# DSO_RAM.net
KiCad netlist of a schematic drawn in Altium Designer
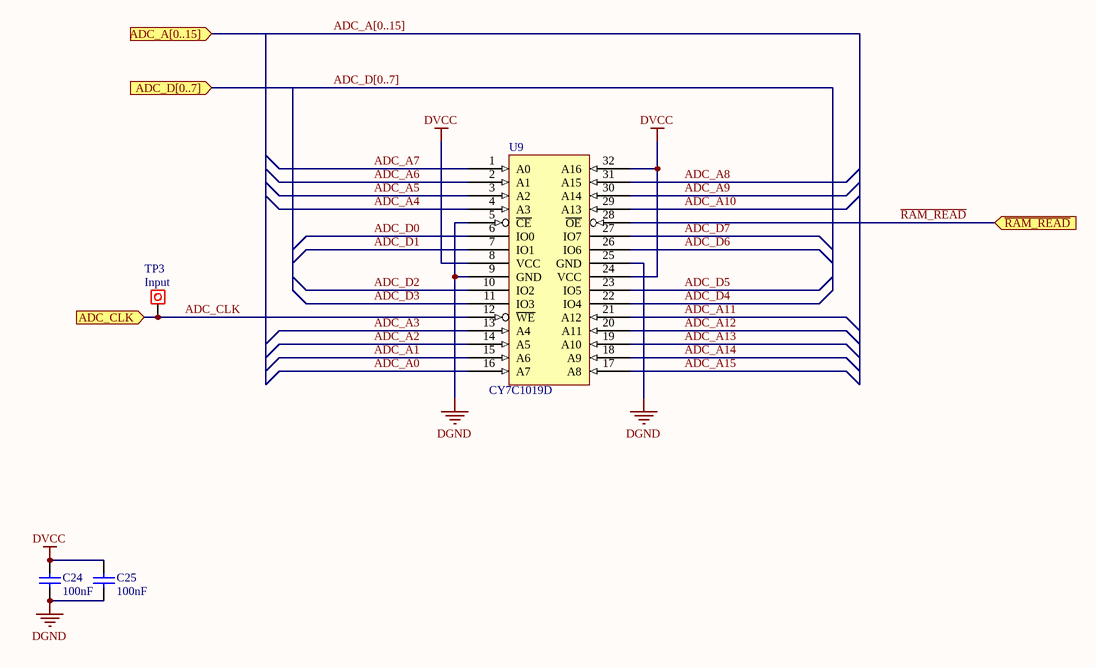
[diagram p0: DSO_RAM.SchDoc]

(export (version "E")
  (design (tool "Eeschema 10.0.6"))
  (components
    (comp (ref "C24")
      (value "100nF")
      (footprint "0805C")
      (description "Capacitor")
      (fields (field (name "REVIEWED BY") "RM - 2018/08/05"))
      (libsource (lib "DSO") (part "C"))
    )
    (comp (ref "C25")
      (value "100nF")
      (footprint "0805C")
      (description "Capacitor")
      (fields (field (name "REVIEWED BY") "RM - 2018/08/05"))
      (libsource (lib "DSO") (part "C"))
    )
    (comp (ref "TP3")
      (value "Input")
      (footprint "Testpoin")
      (description "Pad")
      (fields (field (name "Comment") "INPUT"))
      (libsource (lib "DSO") (part "Test Point"))
    )
    (comp (ref "U9")
      (value "CY7C1019D")
      (footprint "TSOP-32")
      (description "SRAM 128k x 8")
      (fields (field (name "REVIEWED BY") "RM - 2018/08/05"))
      (libsource (lib "DSO") (part "CY7C1019D"))
    )
  )
  (nets
    (net (code "1") (name "/ADC_A0") (class "Default")
      (node (ref "U9") (pin "16") (pinfunction "A7_16") (pintype "input"))
    )
    (net (code "2") (name "/ADC_A1") (class "Default")
      (node (ref "U9") (pin "15") (pinfunction "A6_15") (pintype "input"))
    )
    (net (code "3") (name "/ADC_A2") (class "Default")
      (node (ref "U9") (pin "14") (pinfunction "A5_14") (pintype "input"))
    )
    (net (code "4") (name "/ADC_A3") (class "Default")
      (node (ref "U9") (pin "13") (pinfunction "A4_13") (pintype "input"))
    )
    (net (code "5") (name "/ADC_A4") (class "Default")
      (node (ref "U9") (pin "4") (pinfunction "A3_4") (pintype "input"))
    )
    (net (code "6") (name "/ADC_A5") (class "Default")
      (node (ref "U9") (pin "3") (pinfunction "A2_3") (pintype "input"))
    )
    (net (code "7") (name "/ADC_A6") (class "Default")
      (node (ref "U9") (pin "2") (pinfunction "A1_2") (pintype "input"))
    )
    (net (code "8") (name "/ADC_A7") (class "Default")
      (node (ref "U9") (pin "1") (pinfunction "A0_1") (pintype "input"))
    )
    (net (code "9") (name "/ADC_A8") (class "Default")
      (node (ref "U9") (pin "31") (pinfunction "A15_31") (pintype "input"))
    )
    (net (code "10") (name "/ADC_A9") (class "Default")
      (node (ref "U9") (pin "30") (pinfunction "A14_30") (pintype "input"))
    )
    (net (code "11") (name "/ADC_A10") (class "Default")
      (node (ref "U9") (pin "29") (pinfunction "A13_29") (pintype "input"))
    )
    (net (code "12") (name "/ADC_A11") (class "Default")
      (node (ref "U9") (pin "21") (pinfunction "A12_21") (pintype "input"))
    )
    (net (code "13") (name "/ADC_A12") (class "Default")
      (node (ref "U9") (pin "20") (pinfunction "A11_20") (pintype "input"))
    )
    (net (code "14") (name "/ADC_A13") (class "Default")
      (node (ref "U9") (pin "19") (pinfunction "A10_19") (pintype "input"))
    )
    (net (code "15") (name "/ADC_A14") (class "Default")
      (node (ref "U9") (pin "18") (pinfunction "A9_18") (pintype "input"))
    )
    (net (code "16") (name "/ADC_A15") (class "Default")
      (node (ref "U9") (pin "17") (pinfunction "A8_17") (pintype "input"))
    )
    (net (code "18") (name "/ADC_CLK") (class "Default")
      (node (ref "TP3") (pin "1") (pintype "passive"))
      (node (ref "U9") (pin "12") (pinfunction "~{WE}_12") (pintype "input"))
    )
    (net (code "19") (name "/ADC_D0") (class "Default")
      (node (ref "U9") (pin "6") (pinfunction "IO0_6") (pintype "tri_state"))
    )
    (net (code "20") (name "/ADC_D1") (class "Default")
      (node (ref "U9") (pin "7") (pinfunction "IO1_7") (pintype "tri_state"))
    )
    (net (code "21") (name "/ADC_D2") (class "Default")
      (node (ref "U9") (pin "10") (pinfunction "IO2_10") (pintype "tri_state"))
    )
    (net (code "22") (name "/ADC_D3") (class "Default")
      (node (ref "U9") (pin "11") (pinfunction "IO3_11") (pintype "tri_state"))
    )
    (net (code "23") (name "/ADC_D4") (class "Default")
      (node (ref "U9") (pin "22") (pinfunction "IO4_22") (pintype "tri_state"))
    )
    (net (code "24") (name "/ADC_D5") (class "Default")
      (node (ref "U9") (pin "23") (pinfunction "IO5_23") (pintype "tri_state"))
    )
    (net (code "25") (name "/ADC_D6") (class "Default")
      (node (ref "U9") (pin "26") (pinfunction "IO6_26") (pintype "tri_state"))
    )
    (net (code "26") (name "/ADC_D7") (class "Default")
      (node (ref "U9") (pin "27") (pinfunction "IO7_27") (pintype "tri_state"))
    )
    (net (code "28") (name "/~{RAM_READ}") (class "Default")
      (node (ref "U9") (pin "28") (pinfunction "~{OE}_28") (pintype "input"))
    )
    (net (code "29") (name "DGND") (class "Default")
      (node (ref "C24") (pin "2") (pinfunction "2_2") (pintype "passive"))
      (node (ref "C25") (pin "2") (pinfunction "2_2") (pintype "passive"))
      (node (ref "U9") (pin "25") (pinfunction "GND_25") (pintype "passive"))
      (node (ref "U9") (pin "5") (pinfunction "~{CE}_5") (pintype "input"))
      (node (ref "U9") (pin "9") (pinfunction "GND_9") (pintype "passive"))
    )
    (net (code "30") (name "DVCC") (class "Default")
      (node (ref "C24") (pin "1") (pinfunction "1_1") (pintype "passive"))
      (node (ref "C25") (pin "1") (pinfunction "1_1") (pintype "passive"))
      (node (ref "U9") (pin "24") (pinfunction "VCC_24") (pintype "passive"))
      (node (ref "U9") (pin "32") (pinfunction "A16_32") (pintype "input"))
      (node (ref "U9") (pin "8") (pinfunction "VCC_8") (pintype "passive"))
    )
  )
)
